# espism-v4.net
KiCad netlist of a schematic drawn in EAGLE
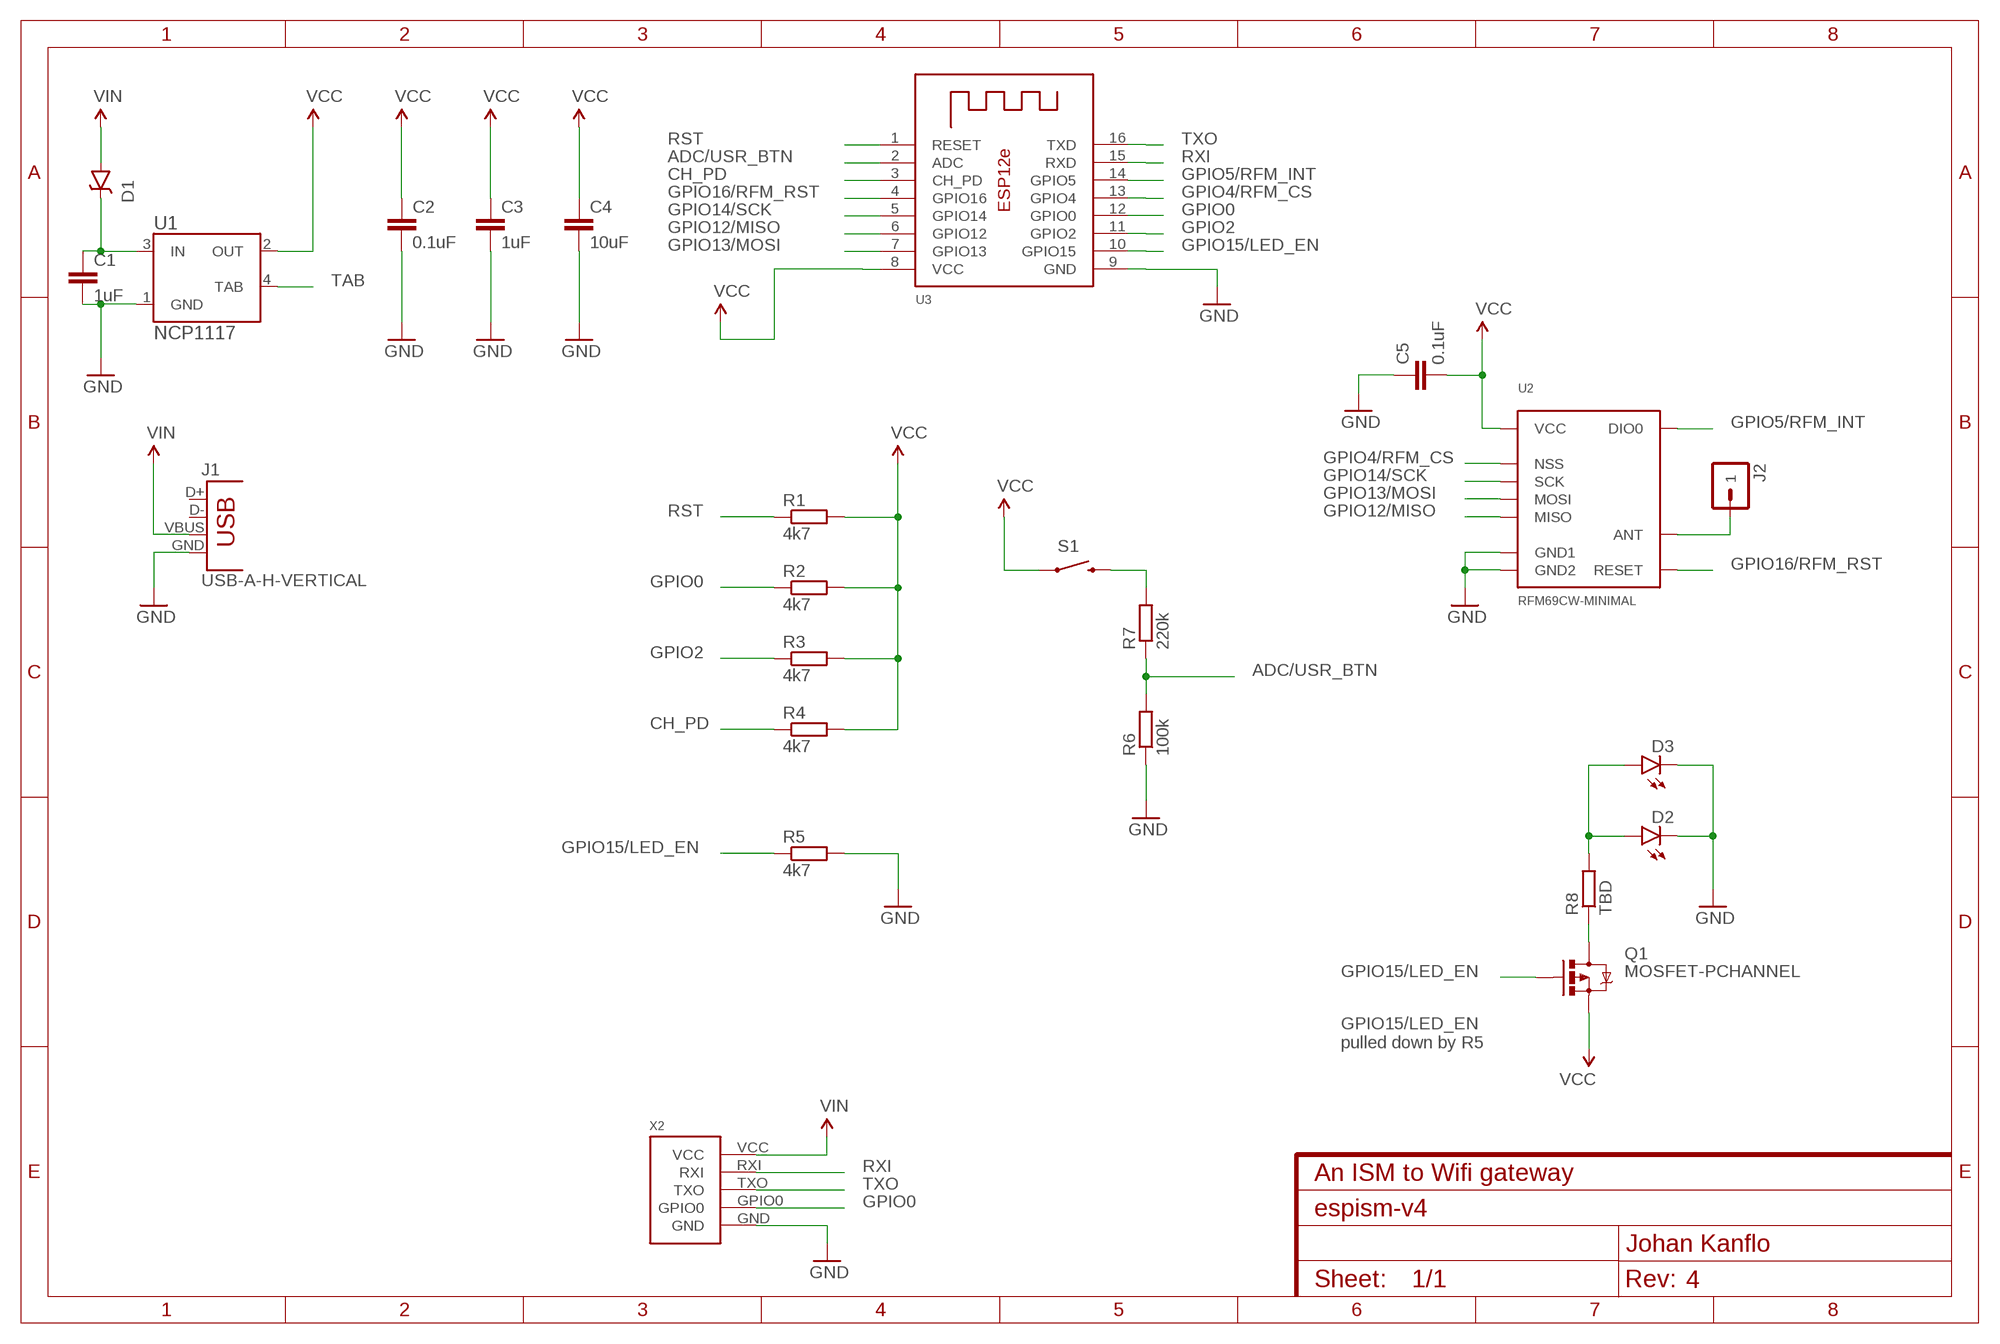
[diagram p0: schematic, sheet 1]

(export (version "E")
  (design (tool "Eeschema 10.0.6"))
  (components
    (comp (ref "C1")
      (value "1uF")
      (footprint "eagle-import:0603-CAP")
      (libsource (lib "eagle-import") (part "CAP0603-CAP"))
    )
    (comp (ref "C2")
      (value "0.1uF")
      (footprint "eagle-import:0603-CAP")
      (libsource (lib "eagle-import") (part "CAP0603-CAP"))
    )
    (comp (ref "C3")
      (value "1uF")
      (footprint "eagle-import:0603-CAP")
      (libsource (lib "eagle-import") (part "CAP0603-CAP"))
    )
    (comp (ref "C4")
      (value "10uF")
      (footprint "eagle-import:0603-CAP")
      (libsource (lib "eagle-import") (part "CAP0603-CAP"))
    )
    (comp (ref "C5")
      (value "0.1uF")
      (footprint "eagle-import:0603-CAP")
      (libsource (lib "eagle-import") (part "CAP0603-CAP"))
    )
    (comp (ref "D1")
      (value "DIODE-SCHOTTKYSOD-123FL")
      (footprint "eagle-import:SOD-123FL")
      (libsource (lib "eagle-import") (part "DIODE-SCHOTTKYSOD-123FL"))
    )
    (comp (ref "D2")
      (value "LED0603")
      (footprint "eagle-import:LED-0603")
      (libsource (lib "eagle-import") (part "LED0603"))
    )
    (comp (ref "D3")
      (value "LED0603")
      (footprint "eagle-import:LED-0603")
      (libsource (lib "eagle-import") (part "LED0603"))
    )
    (comp (ref "J1")
      (value "USB-A-H-VERTICAL")
      (footprint "eagle-import:USB-A-H-VERTICAL")
      (libsource (lib "eagle-import") (part "USB-A-H-VERTICAL"))
    )
    (comp (ref "J2")
      (value "M01-ANTENNA")
      (footprint "eagle-import:1X01-ANTENNA")
      (libsource (lib "eagle-import") (part "M01-ANTENNA"))
    )
    (comp (ref "Q1")
      (value "MOSFET-PCHANNEL")
      (footprint "eagle-import:SOT23-3")
      (libsource (lib "eagle-import") (part "MOSFET-PCHANNEL"))
    )
    (comp (ref "R1")
      (value "4k7")
      (footprint "eagle-import:R0603")
      (libsource (lib "eagle-import") (part "R-EU_R0603"))
    )
    (comp (ref "R2")
      (value "4k7")
      (footprint "eagle-import:R0603")
      (libsource (lib "eagle-import") (part "R-EU_R0603"))
    )
    (comp (ref "R3")
      (value "4k7")
      (footprint "eagle-import:R0603")
      (libsource (lib "eagle-import") (part "R-EU_R0603"))
    )
    (comp (ref "R4")
      (value "4k7")
      (footprint "eagle-import:R0603")
      (libsource (lib "eagle-import") (part "R-EU_R0603"))
    )
    (comp (ref "R5")
      (value "4k7")
      (footprint "eagle-import:R0603")
      (libsource (lib "eagle-import") (part "R-EU_R0603"))
    )
    (comp (ref "R6")
      (value "100k")
      (footprint "eagle-import:R0603")
      (libsource (lib "eagle-import") (part "R-EU_R0603"))
    )
    (comp (ref "R7")
      (value "220k")
      (footprint "eagle-import:R0603")
      (libsource (lib "eagle-import") (part "R-EU_R0603"))
    )
    (comp (ref "R8")
      (value "TBD")
      (footprint "eagle-import:R0603")
      (libsource (lib "eagle-import") (part "R-EU_R0603"))
    )
    (comp (ref "S1")
      (value "SWITCH-MOMENTARY-2SMD-1101NE")
      (footprint "eagle-import:TACTILE-SWITCH-1101NE")
      (libsource (lib "eagle-import") (part "SWITCH-MOMENTARY-2SMD-1101NE"))
    )
    (comp (ref "U1")
      (value "NCP1117")
      (footprint "eagle-import:SOT223")
      (libsource (lib "eagle-import") (part "NCP1117"))
    )
    (comp (ref "U2")
      (value "RFM69CW-MINIMAL")
      (footprint "eagle-import:RFM69CW-MINIMAL")
      (libsource (lib "eagle-import") (part "RFM69CW-MINIMAL"))
    )
    (comp (ref "U3")
      (value "ESP-12E")
      (footprint "eagle-import:ESP-12E")
      (libsource (lib "eagle-import") (part "ESP-12E"))
    )
    (comp (ref "X2")
      (value "ESPROGESPROG-DEVICE")
      (footprint "eagle-import:ESPROG")
      (libsource (lib "eagle-import") (part "ESPROGESPROG-DEVICE"))
    )
  )
  (nets
    (net (code "1") (name "/ADC{slash}USR_BTN") (class "Default")
      (node (ref "R6") (pin "2") (pinfunction "2_2") (pintype "passive"))
      (node (ref "R7") (pin "1") (pinfunction "1_1") (pintype "passive"))
      (node (ref "U3") (pin "2") (pinfunction "ADC_2") (pintype "passive"))
    )
    (net (code "2") (name "/CH_PD") (class "Default")
      (node (ref "R4") (pin "1") (pinfunction "1_1") (pintype "passive"))
      (node (ref "U3") (pin "3") (pinfunction "CH_PD_3") (pintype "input"))
    )
    (net (code "3") (name "/GPIO0") (class "Default")
      (node (ref "R2") (pin "1") (pinfunction "1_1") (pintype "passive"))
      (node (ref "U3") (pin "12") (pinfunction "GPIO0_12") (pintype "bidirectional"))
      (node (ref "X2") (pin "GPIO0") (pinfunction "GPIO0_GPIO0") (pintype "bidirectional"))
    )
    (net (code "4") (name "/GPIO2") (class "Default")
      (node (ref "R3") (pin "1") (pinfunction "1_1") (pintype "passive"))
      (node (ref "U3") (pin "11") (pinfunction "GPIO2_11") (pintype "bidirectional"))
    )
    (net (code "5") (name "/GPIO4{slash}RFM_CS") (class "Default")
      (node (ref "U2") (pin "NSS") (pinfunction "NSS_NSS") (pintype "input"))
      (node (ref "U3") (pin "13") (pinfunction "GPIO4_13") (pintype "bidirectional"))
    )
    (net (code "6") (name "/GPIO5{slash}RFM_INT") (class "Default")
      (node (ref "U2") (pin "DIO0") (pinfunction "DIO0_DIO0") (pintype "open_collector"))
      (node (ref "U3") (pin "14") (pinfunction "GPIO5_14") (pintype "bidirectional"))
    )
    (net (code "7") (name "/GPIO12{slash}MISO") (class "Default")
      (node (ref "U2") (pin "MISO") (pinfunction "MISO_MISO") (pintype "output"))
      (node (ref "U3") (pin "6") (pinfunction "GPIO12_6") (pintype "bidirectional"))
    )
    (net (code "8") (name "/GPIO13{slash}MOSI") (class "Default")
      (node (ref "U2") (pin "MOSI") (pinfunction "MOSI_MOSI") (pintype "input"))
      (node (ref "U3") (pin "7") (pinfunction "GPIO13_7") (pintype "bidirectional"))
    )
    (net (code "9") (name "/GPIO14{slash}SCK") (class "Default")
      (node (ref "U2") (pin "SCK") (pinfunction "SCK_SCK") (pintype "input"))
      (node (ref "U3") (pin "5") (pinfunction "GPIO14_5") (pintype "bidirectional"))
    )
    (net (code "10") (name "/GPIO15{slash}LED_EN") (class "Default")
      (node (ref "Q1") (pin "1") (pinfunction "G_1") (pintype "passive"))
      (node (ref "R5") (pin "1") (pinfunction "1_1") (pintype "passive"))
      (node (ref "U3") (pin "10") (pinfunction "GPIO15_10") (pintype "bidirectional"))
    )
    (net (code "11") (name "/GPIO16{slash}RFM_RST") (class "Default")
      (node (ref "U2") (pin "RESET") (pinfunction "RESET_RESET") (pintype "bidirectional"))
      (node (ref "U3") (pin "4") (pinfunction "GPIO16_4") (pintype "bidirectional"))
    )
    (net (code "12") (name "/RST") (class "Default")
      (node (ref "R1") (pin "1") (pinfunction "1_1") (pintype "passive"))
      (node (ref "U3") (pin "1") (pinfunction "RESET_1") (pintype "input"))
    )
    (net (code "13") (name "/RXI") (class "Default")
      (node (ref "U3") (pin "15") (pinfunction "RXD_15") (pintype "input"))
      (node (ref "X2") (pin "RXI") (pinfunction "RXI_RXI") (pintype "bidirectional"))
    )
    (net (code "14") (name "/TAB") (class "Default")
      (node (ref "U1") (pin "4") (pinfunction "TAB_4") (pintype "bidirectional"))
    )
    (net (code "15") (name "/TXO") (class "Default")
      (node (ref "U3") (pin "16") (pinfunction "TXD_16") (pintype "output"))
      (node (ref "X2") (pin "TXO") (pinfunction "TXO_TXO") (pintype "bidirectional"))
    )
    (net (code "16") (name "GND") (class "Default")
      (node (ref "C1") (pin "2") (pinfunction "2_2") (pintype "passive"))
      (node (ref "C2") (pin "2") (pinfunction "2_2") (pintype "passive"))
      (node (ref "C3") (pin "2") (pinfunction "2_2") (pintype "passive"))
      (node (ref "C4") (pin "2") (pinfunction "2_2") (pintype "passive"))
      (node (ref "C5") (pin "1") (pinfunction "1_1") (pintype "passive"))
      (node (ref "D2") (pin "C") (pinfunction "C_C") (pintype "passive"))
      (node (ref "D3") (pin "C") (pinfunction "C_C") (pintype "passive"))
      (node (ref "J1") (pin "GND") (pinfunction "GND_GND") (pintype "bidirectional"))
      (node (ref "R5") (pin "2") (pinfunction "2_2") (pintype "passive"))
      (node (ref "R6") (pin "1") (pinfunction "1_1") (pintype "passive"))
      (node (ref "U1") (pin "1") (pinfunction "GND_1") (pintype "bidirectional"))
      (node (ref "U2") (pin "GND@1") (pinfunction "GND1_GND@1") (pintype "power_in"))
      (node (ref "U2") (pin "GND@2") (pinfunction "GND2_GND@2") (pintype "power_in"))
      (node (ref "U3") (pin "9") (pinfunction "GND_9") (pintype "power_in"))
      (node (ref "X2") (pin "GND") (pinfunction "GND_GND") (pintype "bidirectional"))
    )
    (net (code "17") (name "Net-(D2-PadA)") (class "Default")
      (node (ref "D2") (pin "A") (pinfunction "A_A") (pintype "passive"))
      (node (ref "D3") (pin "A") (pinfunction "A_A") (pintype "passive"))
      (node (ref "R8") (pin "2") (pinfunction "2_2") (pintype "passive"))
    )
    (net (code "18") (name "Net-(J2-Pad1)") (class "Default")
      (node (ref "J2") (pin "1") (pinfunction "1_1") (pintype "bidirectional"))
      (node (ref "U2") (pin "ANT") (pinfunction "ANT_ANT") (pintype "passive"))
    )
    (net (code "19") (name "Net-(Q1-D)") (class "Default")
      (node (ref "Q1") (pin "3") (pinfunction "D_3") (pintype "passive"))
      (node (ref "R8") (pin "1") (pinfunction "1_1") (pintype "passive"))
    )
    (net (code "20") (name "Net-(R7-Pad2)") (class "Default")
      (node (ref "R7") (pin "2") (pinfunction "2_2") (pintype "passive"))
      (node (ref "S1") (pin "2") (pinfunction "2_2") (pintype "passive"))
    )
    (net (code "21") (name "Net-(U1-IN)") (class "Default")
      (node (ref "C1") (pin "1") (pinfunction "1_1") (pintype "passive"))
      (node (ref "D1") (pin "C") (pinfunction "C_C") (pintype "passive"))
      (node (ref "U1") (pin "3") (pinfunction "IN_3") (pintype "bidirectional"))
    )
    (net (code "22") (name "VCC") (class "Default")
      (node (ref "C2") (pin "1") (pinfunction "1_1") (pintype "passive"))
      (node (ref "C3") (pin "1") (pinfunction "1_1") (pintype "passive"))
      (node (ref "C4") (pin "1") (pinfunction "1_1") (pintype "passive"))
      (node (ref "C5") (pin "2") (pinfunction "2_2") (pintype "passive"))
      (node (ref "Q1") (pin "2") (pinfunction "S_2") (pintype "passive"))
      (node (ref "R1") (pin "2") (pinfunction "2_2") (pintype "passive"))
      (node (ref "R2") (pin "2") (pinfunction "2_2") (pintype "passive"))
      (node (ref "R3") (pin "2") (pinfunction "2_2") (pintype "passive"))
      (node (ref "R4") (pin "2") (pinfunction "2_2") (pintype "passive"))
      (node (ref "S1") (pin "1") (pinfunction "1_1") (pintype "passive"))
      (node (ref "U1") (pin "2") (pinfunction "OUT_2") (pintype "bidirectional"))
      (node (ref "U2") (pin "VDD") (pinfunction "VCC_VDD") (pintype "power_in"))
      (node (ref "U3") (pin "8") (pinfunction "VCC_8") (pintype "power_in"))
    )
    (net (code "23") (name "VIN") (class "Default")
      (node (ref "D1") (pin "A") (pinfunction "A_A") (pintype "passive"))
      (node (ref "J1") (pin "VBUS") (pinfunction "VBUS_VBUS") (pintype "bidirectional"))
      (node (ref "X2") (pin "VCC") (pinfunction "VCC_VCC") (pintype "bidirectional"))
    )
    (net (code "24") (name "unconnected-(J1-PadD+)") (class "Default")
      (node (ref "J1") (pin "D+") (pinfunction "D+_D+") (pintype "bidirectional"))
    )
    (net (code "25") (name "unconnected-(J1-PadD-)") (class "Default")
      (node (ref "J1") (pin "D-") (pinfunction "D-_D-") (pintype "bidirectional"))
    )
  )
)
